# AUTO_D_SCHEMATICS.net
KiCad netlist of a schematic drawn in Altium Designer
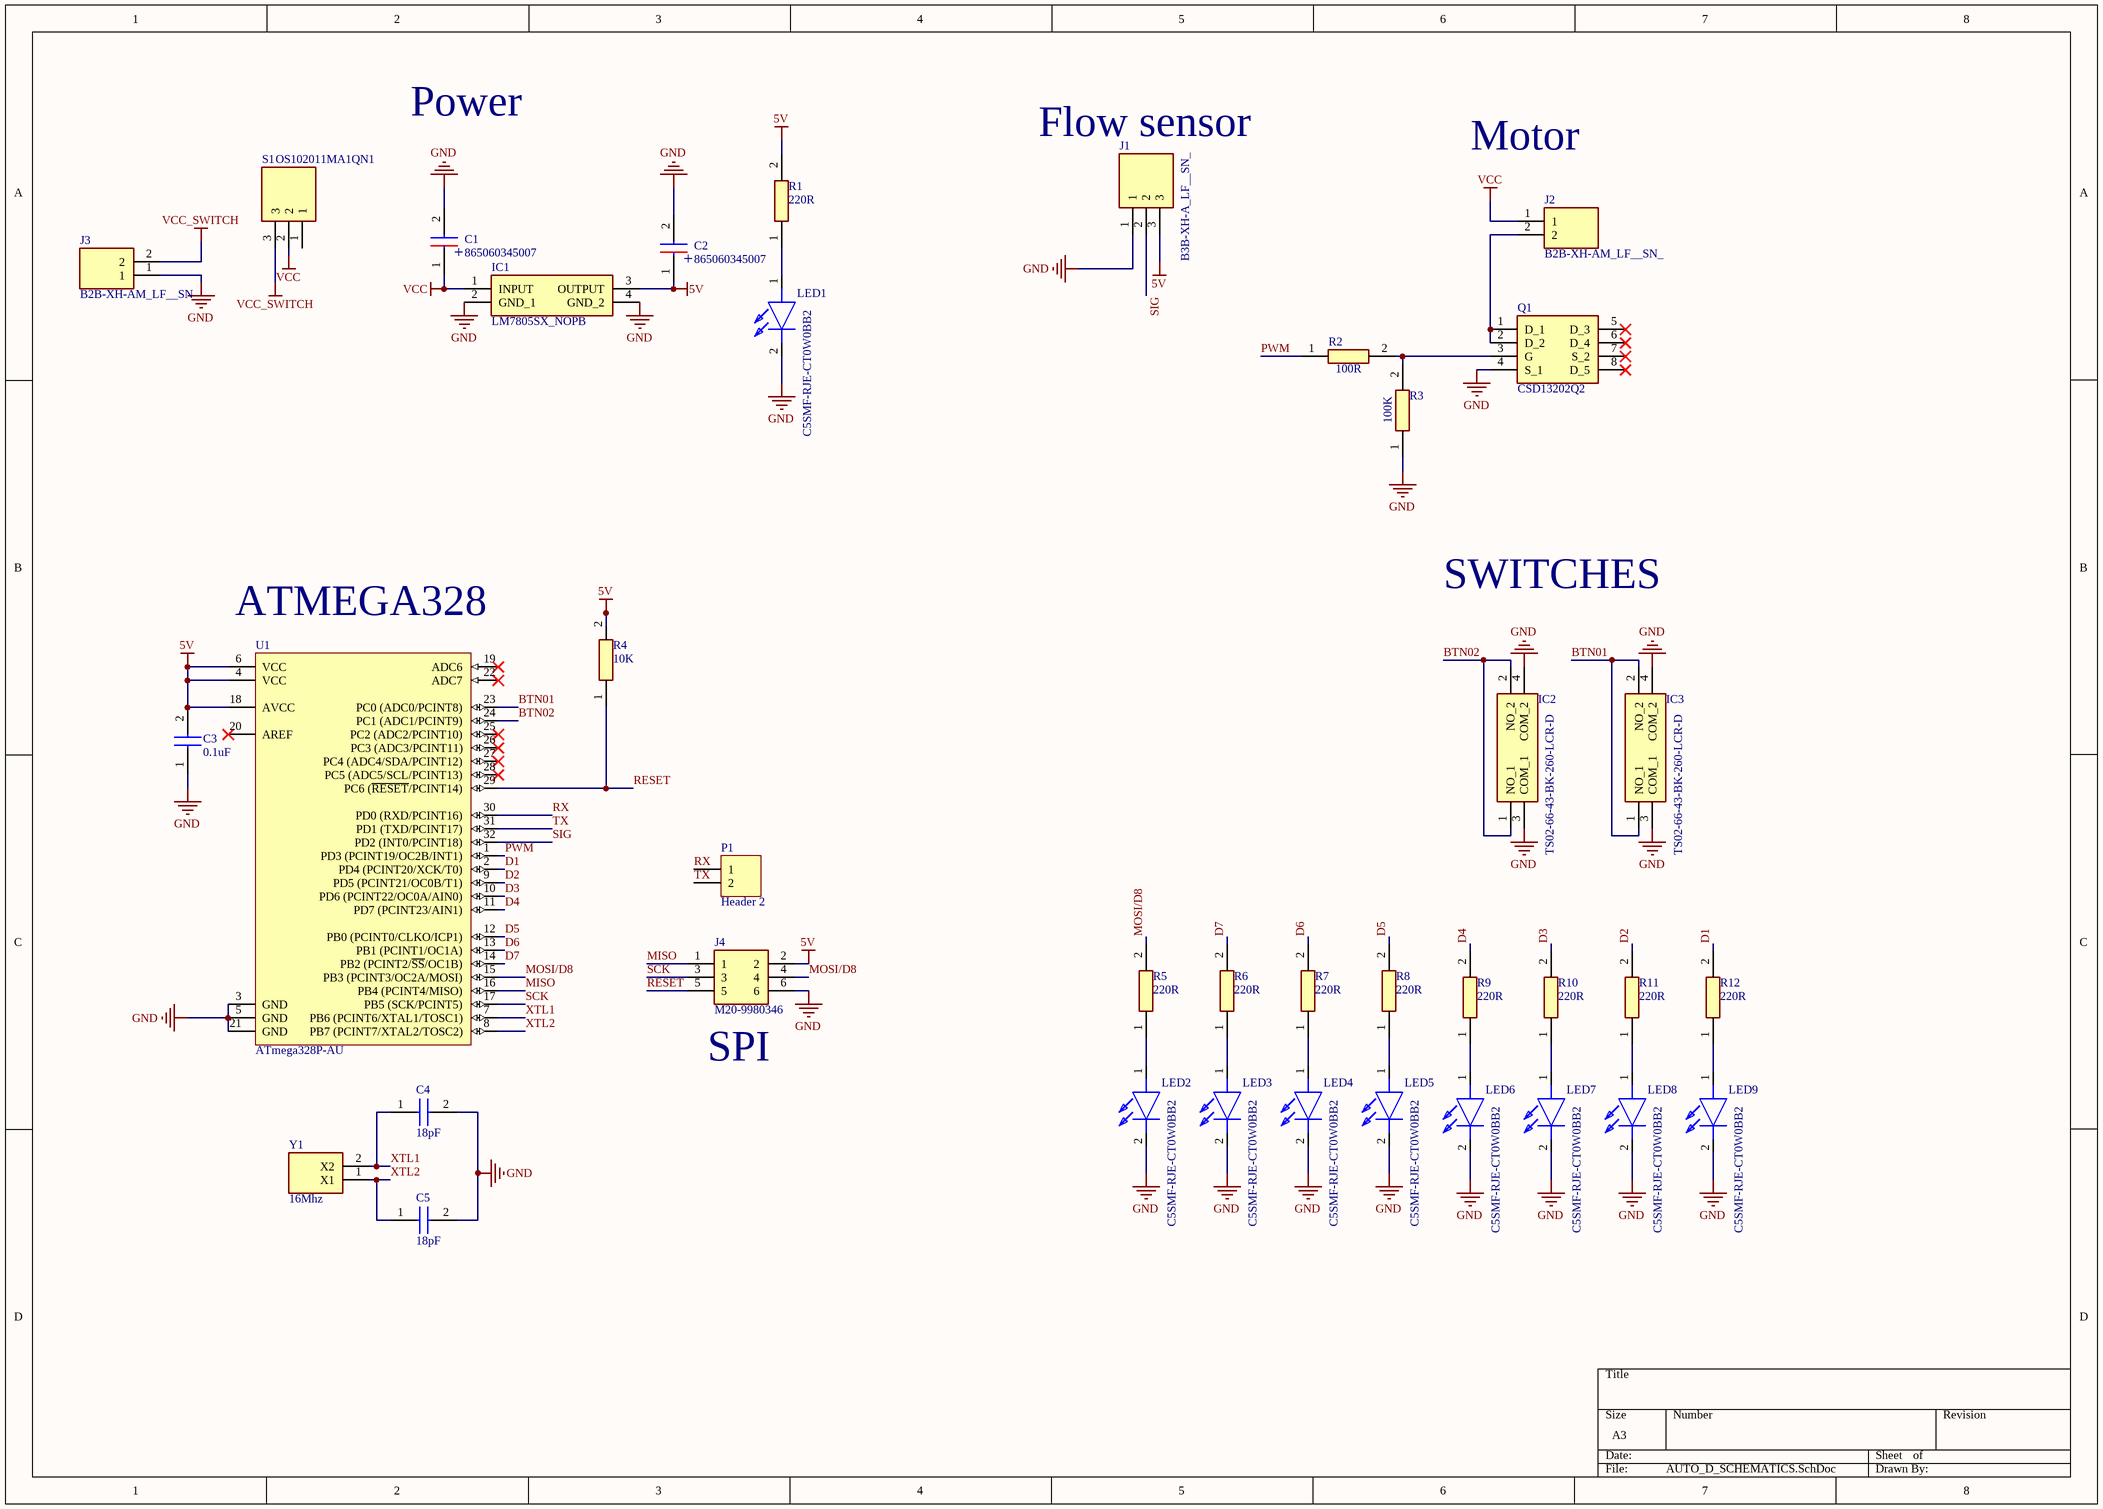
[diagram p0: AUTO_D_SCHEMATICS.SchDoc]

(export (version "E")
  (design (tool "Eeschema 10.0.6"))
  (components
    (comp (ref "C1")
      (value "865060345007")
      (footprint "SamacSys:CAPAE660X770N")
      (description "Capacitor")
      (fields (field (name "MOUSER PART NUMBER") "710-865060345007"))
      (libsource (lib "AUTO_D_SCHEMATICS") (part "865060345007"))
    )
    (comp (ref "C2")
      (value "865060345007")
      (footprint "SamacSys:CAPAE660X770N")
      (description "Capacitor")
      (fields (field (name "MOUSER PART NUMBER") "710-865060345007"))
      (libsource (lib "AUTO_D_SCHEMATICS") (part "865060345007"))
    )
    (comp (ref "C3")
      (value "0.1uF")
      (footprint "CAPC2012X88N")
      (description "Capacitor")
      (fields
        (field (name "MANUFACTURER_PART_NUMBER") "C0805C104K9RACAUTO")
        (field (name "MOUSER PART NUMBER") "80-C0805C104K9RAUTO")
      )
      (libsource (lib "SamacSys") (part "C0805C104K9RACAUTO"))
    )
    (comp (ref "C4")
      (value "18pF")
      (footprint "CAPC2012X135N")
      (description "Capacitor")
      (fields (field (name "MANUFACTURER_PART_NUMBER") "C0603C180M5HACTU"))
      (libsource (lib "Sensor_Board_V1") (part "C0603C180M5HACTU"))
    )
    (comp (ref "C5")
      (value "18pF")
      (footprint "CAPC2012X135N")
      (description "Capacitor")
      (fields (field (name "MANUFACTURER_PART_NUMBER") "C0603C180M5HACTU"))
      (libsource (lib "Sensor_Board_V1") (part "C0603C180M5HACTU"))
    )
    (comp (ref "IC1")
      (value "LM7805SX_NOPB")
      (footprint "SamacSys:KTT0003B")
      (description "Integrated Circuit")
      (fields
        (field (name "MANUFACTURER_PART_NUMBER") "LM7805SX/NOPB")
        (field (name "MOUSER PART NUMBER") "595-LM7805SX/NOPB")
      )
      (libsource (lib "AUTO_D_SCHEMATICS") (part "LM7805SX_NOPB"))
    )
    (comp (ref "IC2")
      (value "TS02-66-43-BK-260-LCR-D")
      (footprint "SamacSys:TS026643BK260LCRD")
      (description "Integrated Circuit")
      (fields (field (name "MOUSER PART NUMBER") "179-TS026643BK260LCR"))
      (libsource (lib "*") (part "TS02-66-43-BK-260-LCR-D"))
    )
    (comp (ref "IC3")
      (value "TS02-66-43-BK-260-LCR-D")
      (footprint "SamacSys:TS026643BK260LCRD")
      (description "Integrated Circuit")
      (fields (field (name "MOUSER PART NUMBER") "179-TS026643BK260LCR"))
      (libsource (lib "*") (part "TS02-66-43-BK-260-LCR-D"))
    )
    (comp (ref "J1")
      (value "B3B-XH-A_LF__SN_")
      (footprint "SamacSys:B3BXHALFSN")
      (description "Connector")
      (fields (field (name "MANUFACTURER_PART_NUMBER") "B3B-XH-A(LF)(SN)"))
      (libsource (lib "SamacSys") (part "B3B-XH-A_LF__SN_"))
    )
    (comp (ref "J2")
      (value "B2B-XH-AM_LF__SN_")
      (footprint "B2BXHAMLFSN")
      (description "Connector")
      (fields (field (name "MANUFACTURER_PART_NUMBER") "B2B-XH-AM(LF)(SN)"))
      (libsource (lib "AUTO_D_SCHEMATICS") (part "B2B-XH-AM_LF__SN_"))
    )
    (comp (ref "J3")
      (value "B2B-XH-AM_LF__SN_")
      (footprint "B2BXHAMLFSN")
      (description "Connector")
      (fields (field (name "MANUFACTURER_PART_NUMBER") "B2B-XH-AM(LF)(SN)"))
      (libsource (lib "") (part "B2B-XH-AM_LF__SN__1"))
    )
    (comp (ref "J4")
      (value "M20-9980346")
      (footprint "HDRV6W64P254_2X3_762X508X868P")
      (description "Connector")
      (fields (field (name "MOUSER PART NUMBER") "855-M20-9980346"))
      (libsource (lib "SamacSys") (part "M20-9980346"))
    )
    (comp (ref "LED1")
      (value "C5SMF-RJE-CT0W0BB2")
      (footprint "SamacSys:C5SMFRJECT0W0BB2")
      (description "LED")
      (fields (field (name "MOUSER PART NUMBER") "941-C5SMFRJECT0W0BB2"))
      (libsource (lib "*") (part "C5SMF-RJE-CT0W0BB2"))
    )
    (comp (ref "LED2")
      (value "C5SMF-RJE-CT0W0BB2")
      (footprint "SamacSys:C5SMFRJECT0W0BB2")
      (description "LED")
      (fields (field (name "MOUSER PART NUMBER") "941-C5SMFRJECT0W0BB2"))
      (libsource (lib "*") (part "C5SMF-RJE-CT0W0BB2"))
    )
    (comp (ref "LED3")
      (value "C5SMF-RJE-CT0W0BB2")
      (footprint "SamacSys:C5SMFRJECT0W0BB2")
      (description "LED")
      (fields (field (name "MOUSER PART NUMBER") "941-C5SMFRJECT0W0BB2"))
      (libsource (lib "*") (part "C5SMF-RJE-CT0W0BB2"))
    )
    (comp (ref "LED4")
      (value "C5SMF-RJE-CT0W0BB2")
      (footprint "SamacSys:C5SMFRJECT0W0BB2")
      (description "LED")
      (fields (field (name "MOUSER PART NUMBER") "941-C5SMFRJECT0W0BB2"))
      (libsource (lib "*") (part "C5SMF-RJE-CT0W0BB2"))
    )
    (comp (ref "LED5")
      (value "C5SMF-RJE-CT0W0BB2")
      (footprint "SamacSys:C5SMFRJECT0W0BB2")
      (description "LED")
      (fields (field (name "MOUSER PART NUMBER") "941-C5SMFRJECT0W0BB2"))
      (libsource (lib "*") (part "C5SMF-RJE-CT0W0BB2"))
    )
    (comp (ref "LED6")
      (value "C5SMF-RJE-CT0W0BB2")
      (footprint "SamacSys:C5SMFRJECT0W0BB2")
      (description "LED")
      (fields (field (name "MOUSER PART NUMBER") "941-C5SMFRJECT0W0BB2"))
      (libsource (lib "*") (part "C5SMF-RJE-CT0W0BB2"))
    )
    (comp (ref "LED7")
      (value "C5SMF-RJE-CT0W0BB2")
      (footprint "SamacSys:C5SMFRJECT0W0BB2")
      (description "LED")
      (fields (field (name "MOUSER PART NUMBER") "941-C5SMFRJECT0W0BB2"))
      (libsource (lib "*") (part "C5SMF-RJE-CT0W0BB2"))
    )
    (comp (ref "LED8")
      (value "C5SMF-RJE-CT0W0BB2")
      (footprint "SamacSys:C5SMFRJECT0W0BB2")
      (description "LED")
      (fields (field (name "MOUSER PART NUMBER") "941-C5SMFRJECT0W0BB2"))
      (libsource (lib "*") (part "C5SMF-RJE-CT0W0BB2"))
    )
    (comp (ref "LED9")
      (value "C5SMF-RJE-CT0W0BB2")
      (footprint "SamacSys:C5SMFRJECT0W0BB2")
      (description "LED")
      (fields (field (name "MOUSER PART NUMBER") "941-C5SMFRJECT0W0BB2"))
      (libsource (lib "*") (part "C5SMF-RJE-CT0W0BB2"))
    )
    (comp (ref "P1")
      (value "Header 2")
      (footprint "HDR1X2")
      (description "Header, 2-Pin")
      (fields (field (name "PUBLISHER") "Altium Limited"))
      (libsource (lib "Miscellaneous Connectors") (part "Header 2"))
    )
    (comp (ref "Q1")
      (value "CSD13202Q2")
      (footprint "SamacSys:CSD16301Q2")
      (description "MOSFET (N-Channel)")
      (fields (field (name "MOUSER PART NUMBER") "595-CSD13202Q2"))
      (libsource (lib "*") (part "CSD13202Q2"))
    )
    (comp (ref "R1")
      (value "220R")
      (footprint "RESC2012X60N")
      (description "Resistor")
      (fields (field (name "MANUFACTURER_PART_NUMBER") "RC0805FR-07220RL"))
      (libsource (lib "AUTO_D_SCHEMATICS") (part "RC0805FR-07220RL"))
    )
    (comp (ref "R2")
      (value "100R")
      (footprint "RESC2012X60N")
      (description "Resistor")
      (fields (field (name "MANUFACTURER_PART_NUMBER") "RC0805FR-07100RL"))
      (libsource (lib "AUTO_D_SCHEMATICS") (part "RC0805FR-07100RL"))
    )
    (comp (ref "R3")
      (value "100K")
      (footprint "RESC2012X60N")
      (description "Resistor")
      (fields (field (name "MANUFACTURER_PART_NUMBER") "RC0805FR-07100KL"))
      (libsource (lib "AUTO_D_SCHEMATICS") (part "RC0805FR-07100KL"))
    )
    (comp (ref "R4")
      (value "10K")
      (footprint "RESC2012X60N")
      (description "Resistor")
      (fields
        (field (name "MANUFACTURER_PART_NUMBER") "CRCW080510K0FKEAC")
        (field (name "MOUSER PART NUMBER") "71-CRCW080510K0FKEAC")
      )
      (libsource (lib "SamacSys") (part "CRCW080510K0FKEAC"))
    )
    (comp (ref "R5")
      (value "220R")
      (footprint "RESC2012X60N")
      (description "Resistor")
      (fields (field (name "MANUFACTURER_PART_NUMBER") "RC0805FR-07220RL"))
      (libsource (lib "AUTO_D_SCHEMATICS") (part "RC0805FR-07220RL"))
    )
    (comp (ref "R6")
      (value "220R")
      (footprint "RESC2012X60N")
      (description "Resistor")
      (fields (field (name "MANUFACTURER_PART_NUMBER") "RC0805FR-07220RL"))
      (libsource (lib "AUTO_D_SCHEMATICS") (part "RC0805FR-07220RL"))
    )
    (comp (ref "R7")
      (value "220R")
      (footprint "RESC2012X60N")
      (description "Resistor")
      (fields (field (name "MANUFACTURER_PART_NUMBER") "RC0805FR-07220RL"))
      (libsource (lib "AUTO_D_SCHEMATICS") (part "RC0805FR-07220RL"))
    )
    (comp (ref "R8")
      (value "220R")
      (footprint "RESC2012X60N")
      (description "Resistor")
      (fields (field (name "MANUFACTURER_PART_NUMBER") "RC0805FR-07220RL"))
      (libsource (lib "AUTO_D_SCHEMATICS") (part "RC0805FR-07220RL"))
    )
    (comp (ref "R9")
      (value "220R")
      (footprint "RESC2012X60N")
      (description "Resistor")
      (fields (field (name "MANUFACTURER_PART_NUMBER") "RC0805FR-07220RL"))
      (libsource (lib "AUTO_D_SCHEMATICS") (part "RC0805FR-07220RL"))
    )
    (comp (ref "R10")
      (value "220R")
      (footprint "RESC2012X60N")
      (description "Resistor")
      (fields (field (name "MANUFACTURER_PART_NUMBER") "RC0805FR-07220RL"))
      (libsource (lib "AUTO_D_SCHEMATICS") (part "RC0805FR-07220RL"))
    )
    (comp (ref "R11")
      (value "220R")
      (footprint "RESC2012X60N")
      (description "Resistor")
      (fields (field (name "MANUFACTURER_PART_NUMBER") "RC0805FR-07220RL"))
      (libsource (lib "AUTO_D_SCHEMATICS") (part "RC0805FR-07220RL"))
    )
    (comp (ref "R12")
      (value "220R")
      (footprint "RESC2012X60N")
      (description "Resistor")
      (fields (field (name "MANUFACTURER_PART_NUMBER") "RC0805FR-07220RL"))
      (libsource (lib "AUTO_D_SCHEMATICS") (part "RC0805FR-07220RL"))
    )
    (comp (ref "S1")
      (value "OS102011MA1QN1")
      (footprint "SamacSys:OS102011MA1QN1")
      (description "Switch")
      (fields (field (name "MOUSER PART NUMBER") "611-OS102011MA1QN1"))
      (libsource (lib "*") (part "OS102011MA1QN1"))
    )
    (comp (ref "U1")
      (value "ATmega328P-AU")
      (footprint "AUTO_D_SCHEMATICS.PcbDo:32-TQFP (7x7)mm")
      (description "8-bit Microcontrollers - MCU 32KB In-system Flash 20MHz 1.8V-5.5V")
      (fields (field (name "MANUFACTURER_PART_NUMBER") "ATMEGA328P-AU"))
      (libsource (lib "MagicLight") (part "ATmega328P-AU"))
    )
    (comp (ref "Y1")
      (value "16Mhz")
      (footprint "ABL2-8.000MHZ-D3W-I-T")
      (description "Crystal or Oscillator")
      (fields (field (name "MANUFACTURER_PART_NUMBER") "ABL-16.000MHZ-B2"))
      (libsource (lib "Sensor_Board_V1") (part "ABL-16.000MHZ-B2"))
    )
  )
  (nets
    (net (code "2") (name "/BTN01") (class "Default")
      (node (ref "IC3") (pin "1") (pinfunction "NO_1_1") (pintype "passive"))
      (node (ref "IC3") (pin "2") (pinfunction "NO_2_2") (pintype "passive"))
      (node (ref "U1") (pin "23") (pinfunction "PC0_(ADC0/PCINT8)_23") (pintype "bidirectional"))
    )
    (net (code "3") (name "/BTN02") (class "Default")
      (node (ref "IC2") (pin "1") (pinfunction "NO_1_1") (pintype "passive"))
      (node (ref "IC2") (pin "2") (pinfunction "NO_2_2") (pintype "passive"))
      (node (ref "U1") (pin "24") (pinfunction "PC1_(ADC1/PCINT9)_24") (pintype "bidirectional"))
    )
    (net (code "4") (name "/D1") (class "Default")
      (node (ref "R12") (pin "2") (pinfunction "2_2") (pintype "passive"))
      (node (ref "U1") (pin "2") (pinfunction "PD4_(PCINT20/XCK/T0)_2") (pintype "bidirectional"))
    )
    (net (code "5") (name "/D2") (class "Default")
      (node (ref "R11") (pin "2") (pinfunction "2_2") (pintype "passive"))
      (node (ref "U1") (pin "9") (pinfunction "PD5_(PCINT21/OC0B/T1)_9") (pintype "bidirectional"))
    )
    (net (code "6") (name "/D3") (class "Default")
      (node (ref "R10") (pin "2") (pinfunction "2_2") (pintype "passive"))
      (node (ref "U1") (pin "10") (pinfunction "PD6_(PCINT22/OC0A/AIN0)_10") (pintype "bidirectional"))
    )
    (net (code "7") (name "/D4") (class "Default")
      (node (ref "R9") (pin "2") (pinfunction "2_2") (pintype "passive"))
      (node (ref "U1") (pin "11") (pinfunction "PD7_(PCINT23/AIN1)_11") (pintype "bidirectional"))
    )
    (net (code "8") (name "/D5") (class "Default")
      (node (ref "R8") (pin "2") (pinfunction "2_2") (pintype "passive"))
      (node (ref "U1") (pin "12") (pinfunction "PB0_(PCINT0/CLKO/ICP1)_12") (pintype "bidirectional"))
    )
    (net (code "9") (name "/D6") (class "Default")
      (node (ref "R7") (pin "2") (pinfunction "2_2") (pintype "passive"))
      (node (ref "U1") (pin "13") (pinfunction "PB1_(PCINT1/OC1A)_13") (pintype "bidirectional"))
    )
    (net (code "10") (name "/D7") (class "Default")
      (node (ref "R6") (pin "2") (pinfunction "2_2") (pintype "passive"))
      (node (ref "U1") (pin "14") (pinfunction "PB2_(PCINT2/~{SS}/OC1B)_14") (pintype "bidirectional"))
    )
    (net (code "11") (name "/MISO") (class "Default")
      (node (ref "J4") (pin "1") (pinfunction "1_1") (pintype "passive"))
      (node (ref "U1") (pin "16") (pinfunction "PB4_(PCINT4/MISO)_16") (pintype "bidirectional"))
    )
    (net (code "12") (name "/MOSI{slash}D8") (class "Default")
      (node (ref "J4") (pin "4") (pinfunction "4_4") (pintype "passive"))
      (node (ref "R5") (pin "2") (pinfunction "2_2") (pintype "passive"))
      (node (ref "U1") (pin "15") (pinfunction "PB3_(PCINT3/OC2A/MOSI)_15") (pintype "bidirectional"))
    )
    (net (code "13") (name "/PWM") (class "Default")
      (node (ref "R2") (pin "1") (pinfunction "1_1") (pintype "passive"))
      (node (ref "U1") (pin "1") (pinfunction "PD3_(PCINT19/OC2B/INT1)_1") (pintype "bidirectional"))
    )
    (net (code "14") (name "/RESET") (class "Default")
      (node (ref "J4") (pin "5") (pinfunction "5_5") (pintype "passive"))
      (node (ref "R4") (pin "1") (pinfunction "1_1") (pintype "passive"))
      (node (ref "U1") (pin "29") (pinfunction "PC6_(~{RESET}/PCINT14)_29") (pintype "bidirectional"))
    )
    (net (code "15") (name "/RX") (class "Default")
      (node (ref "P1") (pin "1") (pinfunction "1_1") (pintype "passive"))
      (node (ref "U1") (pin "30") (pinfunction "PD0_(RXD/PCINT16)_30") (pintype "bidirectional"))
    )
    (net (code "16") (name "/SCK") (class "Default")
      (node (ref "J4") (pin "3") (pinfunction "3_3") (pintype "passive"))
      (node (ref "U1") (pin "17") (pinfunction "PB5_(SCK/PCINT5)_17") (pintype "bidirectional"))
    )
    (net (code "17") (name "/SIG") (class "Default")
      (node (ref "J1") (pin "2") (pinfunction "2_2") (pintype "passive"))
      (node (ref "U1") (pin "32") (pinfunction "PD2_(INT0/PCINT18)_32") (pintype "bidirectional"))
    )
    (net (code "18") (name "/TX") (class "Default")
      (node (ref "P1") (pin "2") (pinfunction "2_2") (pintype "passive"))
      (node (ref "U1") (pin "31") (pinfunction "PD1_(TXD/PCINT17)_31") (pintype "bidirectional"))
    )
    (net (code "19") (name "/XTL1") (class "Default")
      (node (ref "C4") (pin "1") (pinfunction "1_1") (pintype "passive"))
      (node (ref "U1") (pin "7") (pinfunction "PB6_(PCINT6/XTAL1/TOSC1)_7") (pintype "bidirectional"))
      (node (ref "Y1") (pin "2") (pinfunction "X2_2") (pintype "passive"))
    )
    (net (code "20") (name "/XTL2") (class "Default")
      (node (ref "C5") (pin "1") (pinfunction "1_1") (pintype "passive"))
      (node (ref "U1") (pin "8") (pinfunction "PB7_(PCINT7/XTAL2/TOSC2)_8") (pintype "bidirectional"))
      (node (ref "Y1") (pin "1") (pinfunction "X1_1") (pintype "passive"))
    )
    (net (code "21") (name "5V") (class "Default")
      (node (ref "C2") (pin "1") (pinfunction "+_1") (pintype "passive"))
      (node (ref "C3") (pin "2") (pinfunction "2_2") (pintype "passive"))
      (node (ref "IC1") (pin "3") (pinfunction "OUTPUT_3") (pintype "passive"))
      (node (ref "J1") (pin "3") (pinfunction "3_3") (pintype "passive"))
      (node (ref "J4") (pin "2") (pinfunction "2_2") (pintype "passive"))
      (node (ref "R1") (pin "2") (pinfunction "2_2") (pintype "passive"))
      (node (ref "R4") (pin "2") (pinfunction "2_2") (pintype "passive"))
      (node (ref "U1") (pin "18") (pinfunction "AVCC_18") (pintype "power_in"))
      (node (ref "U1") (pin "4") (pinfunction "VCC_4") (pintype "power_in"))
      (node (ref "U1") (pin "6") (pinfunction "VCC_6") (pintype "power_in"))
    )
    (net (code "22") (name "GND") (class "Default")
      (node (ref "C1") (pin "2") (pinfunction "-_2") (pintype "passive"))
      (node (ref "C2") (pin "2") (pinfunction "-_2") (pintype "passive"))
      (node (ref "C3") (pin "1") (pinfunction "1_1") (pintype "passive"))
      (node (ref "C4") (pin "2") (pinfunction "2_2") (pintype "passive"))
      (node (ref "C5") (pin "2") (pinfunction "2_2") (pintype "passive"))
      (node (ref "IC1") (pin "2") (pinfunction "GND_1_2") (pintype "passive"))
      (node (ref "IC1") (pin "4") (pinfunction "GND_2_4") (pintype "passive"))
      (node (ref "IC2") (pin "3") (pinfunction "COM_1_3") (pintype "passive"))
      (node (ref "IC2") (pin "4") (pinfunction "COM_2_4") (pintype "passive"))
      (node (ref "IC3") (pin "3") (pinfunction "COM_1_3") (pintype "passive"))
      (node (ref "IC3") (pin "4") (pinfunction "COM_2_4") (pintype "passive"))
      (node (ref "J1") (pin "1") (pinfunction "1_1") (pintype "passive"))
      (node (ref "J3") (pin "1") (pinfunction "1_1") (pintype "passive"))
      (node (ref "J4") (pin "6") (pinfunction "6_6") (pintype "passive"))
      (node (ref "LED1") (pin "2") (pinfunction "K_2") (pintype "passive"))
      (node (ref "LED2") (pin "2") (pinfunction "K_2") (pintype "passive"))
      (node (ref "LED3") (pin "2") (pinfunction "K_2") (pintype "passive"))
      (node (ref "LED4") (pin "2") (pinfunction "K_2") (pintype "passive"))
      (node (ref "LED5") (pin "2") (pinfunction "K_2") (pintype "passive"))
      (node (ref "LED6") (pin "2") (pinfunction "K_2") (pintype "passive"))
      (node (ref "LED7") (pin "2") (pinfunction "K_2") (pintype "passive"))
      (node (ref "LED8") (pin "2") (pinfunction "K_2") (pintype "passive"))
      (node (ref "LED9") (pin "2") (pinfunction "K_2") (pintype "passive"))
      (node (ref "Q1") (pin "4") (pinfunction "S_1_4") (pintype "passive"))
      (node (ref "R3") (pin "1") (pinfunction "1_1") (pintype "passive"))
      (node (ref "U1") (pin "21") (pinfunction "GND_21") (pintype "power_in"))
      (node (ref "U1") (pin "3") (pinfunction "GND_3") (pintype "power_in"))
      (node (ref "U1") (pin "5") (pinfunction "GND_5") (pintype "power_in"))
    )
    (net (code "23") (name "Net-(LED1-A)") (class "Default")
      (node (ref "LED1") (pin "1") (pinfunction "A_1") (pintype "passive"))
      (node (ref "R1") (pin "1") (pinfunction "1_1") (pintype "passive"))
    )
    (net (code "24") (name "Net-(LED2-A)") (class "Default")
      (node (ref "LED2") (pin "1") (pinfunction "A_1") (pintype "passive"))
      (node (ref "R5") (pin "1") (pinfunction "1_1") (pintype "passive"))
    )
    (net (code "25") (name "Net-(LED3-A)") (class "Default")
      (node (ref "LED3") (pin "1") (pinfunction "A_1") (pintype "passive"))
      (node (ref "R6") (pin "1") (pinfunction "1_1") (pintype "passive"))
    )
    (net (code "26") (name "Net-(LED4-A)") (class "Default")
      (node (ref "LED4") (pin "1") (pinfunction "A_1") (pintype "passive"))
      (node (ref "R7") (pin "1") (pinfunction "1_1") (pintype "passive"))
    )
    (net (code "27") (name "Net-(LED5-A)") (class "Default")
      (node (ref "LED5") (pin "1") (pinfunction "A_1") (pintype "passive"))
      (node (ref "R8") (pin "1") (pinfunction "1_1") (pintype "passive"))
    )
    (net (code "28") (name "Net-(LED6-A)") (class "Default")
      (node (ref "LED6") (pin "1") (pinfunction "A_1") (pintype "passive"))
      (node (ref "R9") (pin "1") (pinfunction "1_1") (pintype "passive"))
    )
    (net (code "29") (name "Net-(LED7-A)") (class "Default")
      (node (ref "LED7") (pin "1") (pinfunction "A_1") (pintype "passive"))
      (node (ref "R10") (pin "1") (pinfunction "1_1") (pintype "passive"))
    )
    (net (code "30") (name "Net-(LED8-A)") (class "Default")
      (node (ref "LED8") (pin "1") (pinfunction "A_1") (pintype "passive"))
      (node (ref "R11") (pin "1") (pinfunction "1_1") (pintype "passive"))
    )
    (net (code "31") (name "Net-(LED9-A)") (class "Default")
      (node (ref "LED9") (pin "1") (pinfunction "A_1") (pintype "passive"))
      (node (ref "R12") (pin "1") (pinfunction "1_1") (pintype "passive"))
    )
    (net (code "32") (name "Net-(Q1-D_1)") (class "Default")
      (node (ref "J2") (pin "2") (pinfunction "2_2") (pintype "passive"))
      (node (ref "Q1") (pin "1") (pinfunction "D_1_1") (pintype "passive"))
      (node (ref "Q1") (pin "2") (pinfunction "D_2_2") (pintype "passive"))
    )
    (net (code "33") (name "Net-(Q1-G)") (class "Default")
      (node (ref "Q1") (pin "3") (pinfunction "G_3") (pintype "passive"))
      (node (ref "R2") (pin "2") (pinfunction "2_2") (pintype "passive"))
      (node (ref "R3") (pin "2") (pinfunction "2_2") (pintype "passive"))
    )
    (net (code "34") (name "VCC") (class "Default")
      (node (ref "C1") (pin "1") (pinfunction "+_1") (pintype "passive"))
      (node (ref "IC1") (pin "1") (pinfunction "INPUT_1") (pintype "passive"))
      (node (ref "J2") (pin "1") (pinfunction "1_1") (pintype "passive"))
      (node (ref "S1") (pin "2") (pinfunction "2_2") (pintype "passive"))
    )
    (net (code "35") (name "VCC_SWITCH") (class "Default")
      (node (ref "J3") (pin "2") (pinfunction "2_2") (pintype "passive"))
      (node (ref "S1") (pin "3") (pinfunction "3_3") (pintype "passive"))
    )
    (net (code "36") (name "unconnected-(Q1-D_3-Pad5)") (class "Default")
      (node (ref "Q1") (pin "5") (pinfunction "D_3_5") (pintype "passive+no_connect"))
    )
    (net (code "37") (name "unconnected-(Q1-D_4-Pad6)") (class "Default")
      (node (ref "Q1") (pin "6") (pinfunction "D_4_6") (pintype "passive+no_connect"))
    )
    (net (code "38") (name "unconnected-(Q1-D_5-Pad8)") (class "Default")
      (node (ref "Q1") (pin "8") (pinfunction "D_5_8") (pintype "passive+no_connect"))
    )
    (net (code "39") (name "unconnected-(Q1-S_2-Pad7)") (class "Default")
      (node (ref "Q1") (pin "7") (pinfunction "S_2_7") (pintype "passive+no_connect"))
    )
    (net (code "40") (name "unconnected-(S1-Pad1)") (class "Default")
      (node (ref "S1") (pin "1") (pinfunction "1_1") (pintype "passive"))
    )
    (net (code "41") (name "unconnected-(U1-ADC6-Pad19)") (class "Default")
      (node (ref "U1") (pin "19") (pinfunction "ADC6_19") (pintype "input+no_connect"))
    )
    (net (code "42") (name "unconnected-(U1-ADC7-Pad22)") (class "Default")
      (node (ref "U1") (pin "22") (pinfunction "ADC7_22") (pintype "input+no_connect"))
    )
    (net (code "43") (name "unconnected-(U1-AREF-Pad20)") (class "Default")
      (node (ref "U1") (pin "20") (pinfunction "AREF_20") (pintype "passive+no_connect"))
    )
    (net (code "44") (name "unconnected-(U1-PC2_(ADC2{slash}PCINT10)-Pad25)") (class "Default")
      (node (ref "U1") (pin "25") (pinfunction "PC2_(ADC2/PCINT10)_25") (pintype "bidirectional+no_connect"))
    )
    (net (code "45") (name "unconnected-(U1-PC3_(ADC3{slash}PCINT11)-Pad26)") (class "Default")
      (node (ref "U1") (pin "26") (pinfunction "PC3_(ADC3/PCINT11)_26") (pintype "bidirectional+no_connect"))
    )
    (net (code "46") (name "unconnected-(U1-PC4_(ADC4{slash}SDA{slash}PCINT12)-Pad27)") (class "Default")
      (node (ref "U1") (pin "27") (pinfunction "PC4_(ADC4/SDA/PCINT12)_27") (pintype "bidirectional+no_connect"))
    )
    (net (code "47") (name "unconnected-(U1-PC5_(ADC5{slash}SCL{slash}PCINT13)-Pad28)") (class "Default")
      (node (ref "U1") (pin "28") (pinfunction "PC5_(ADC5/SCL/PCINT13)_28") (pintype "bidirectional+no_connect"))
    )
  )
)
